# Emulator.net
KiCad netlist of a schematic drawn in Altium Designer
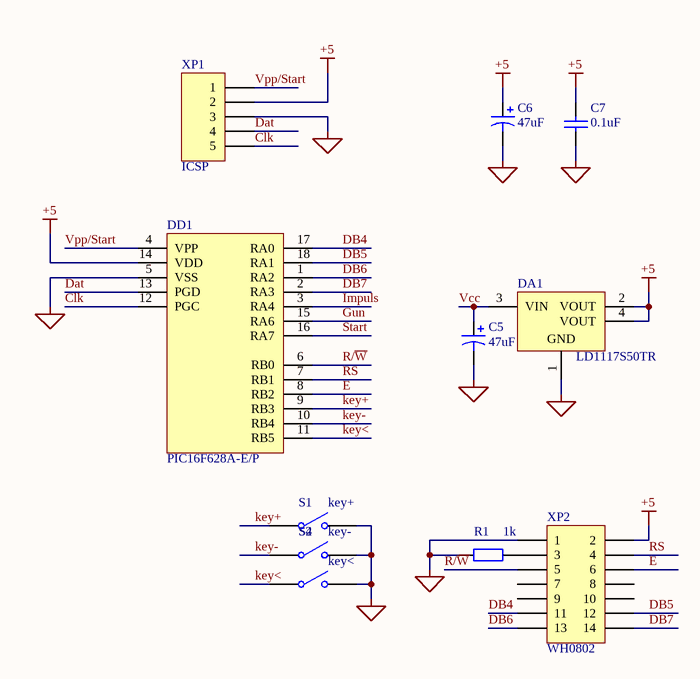
[diagram p0: Emulator.SchDoc]

(export (version "E")
  (design (tool "Eeschema 10.0.6"))
  (components
    (comp (ref "C5")
      (value "47uF")
      (footprint "TC3528-1411")
      (description "Polarized Capacitor (Radial)")
      (fields (field (name "Comment") "Cap Pol1") (field (name "PUBLISHER") "Altium Limited"))
      (libsource (lib "Miscellaneous Devices") (part "Cap Pol1"))
    )
    (comp (ref "C6")
      (value "47uF")
      (footprint "TC3528-1411")
      (description "Polarized Capacitor (Radial)")
      (fields (field (name "Comment") "Cap Pol1") (field (name "PUBLISHER") "Altium Limited"))
      (libsource (lib "Miscellaneous Devices") (part "Cap Pol1"))
    )
    (comp (ref "C7")
      (value "0.1uF")
      (footprint "CAPC2012N")
      (description "Capacitor")
      (fields (field (name "Comment") "Cap") (field (name "PUBLISHER") "Altium Limited"))
      (libsource (lib "Miscellaneous Devices") (part "Cap"))
    )
    (comp (ref "DA1")
      (value "LD1117S50TR")
      (footprint "SOT-223_N")
      (description "Fixed Low Drop Positive Voltage Regulator, 5V, 4-Pin SOT-223, Tape and Reel")
      (libsource (lib "STMicroelectronics Power Management Linear Regulator") (part "LD1117S50TR"))
    )
    (comp (ref "DD1")
      (value "PIC16F628A-E/P")
      (footprint "SOIC127P1030-18N")
      (fields (field (name "PUBLISHER") "Altium Limited"))
      (libsource (lib "Emulator") (part "PIC16F628A-E/P"))
    )
    (comp (ref "R1")
      (value "1k")
      (footprint "RESC2012N")
      (description "Resistor")
      (fields (field (name "Comment") "es2") (field (name "PUBLISHER") "Altium Limited"))
      (libsource (lib "Miscellaneous Devices") (part "Res2"))
    )
    (comp (ref "S1")
      (value "key+")
      (footprint "SPST-2")
      (description "Single-Pole, Single-Throw Switch")
      (fields (field (name "PUBLISHER") "Altium Limited"))
      (libsource (lib "Miscellaneous Devices") (part "SW-SPST"))
    )
    (comp (ref "S2")
      (value "key-")
      (footprint "SPST-2")
      (description "Single-Pole, Single-Throw Switch")
      (fields (field (name "PUBLISHER") "Altium Limited"))
      (libsource (lib "Miscellaneous Devices") (part "SW-SPST"))
    )
    (comp (ref "S4")
      (value "key<")
      (footprint "SPST-2")
      (description "Single-Pole, Single-Throw Switch")
      (fields (field (name "PUBLISHER") "Altium Limited"))
      (libsource (lib "Miscellaneous Devices") (part "SW-SPST"))
    )
    (comp (ref "XP1")
      (value "ICSP")
      (footprint "HDR1X5")
      (description "Header, 5-Pin")
      (fields (field (name "PUBLISHER") "Altium Limited"))
      (libsource (lib "Miscellaneous Connectors") (part "Header 5"))
    )
    (comp (ref "XP2")
      (value "WH0802")
      (footprint "HDR2X7")
      (description "Header, 7-Pin, Dual row")
      (fields (field (name "PUBLISHER") "Altium Limited"))
      (libsource (lib "Miscellaneous Connectors") (part "Header 7X2"))
    )
  )
  (nets
    (net (code "1") (name "+5") (class "Default")
      (node (ref "C6") (pin "1") (pinfunction "1_1") (pintype "passive"))
      (node (ref "C7") (pin "2") (pinfunction "2_2") (pintype "passive"))
      (node (ref "DA1") (pin "2") (pinfunction "VOUT_2") (pintype "power_in"))
      (node (ref "DA1") (pin "4") (pinfunction "VOUT_4") (pintype "power_in"))
      (node (ref "DD1") (pin "14") (pinfunction "VDD_14") (pintype "power_in"))
      (node (ref "XP1") (pin "2") (pinfunction "2_2") (pintype "passive"))
      (node (ref "XP2") (pin "2") (pinfunction "2_2") (pintype "passive"))
    )
    (net (code "2") (name "/Clk") (class "Default")
      (node (ref "DD1") (pin "12") (pinfunction "PGC_12") (pintype "passive"))
      (node (ref "XP1") (pin "5") (pinfunction "5_5") (pintype "passive"))
    )
    (net (code "3") (name "/DB4") (class "Default")
      (node (ref "DD1") (pin "17") (pinfunction "RA0_17") (pintype "passive"))
      (node (ref "XP2") (pin "11") (pinfunction "11_11") (pintype "passive"))
    )
    (net (code "4") (name "/DB5") (class "Default")
      (node (ref "DD1") (pin "18") (pinfunction "RA1_18") (pintype "passive"))
      (node (ref "XP2") (pin "12") (pinfunction "12_12") (pintype "passive"))
    )
    (net (code "5") (name "/DB6") (class "Default")
      (node (ref "DD1") (pin "1") (pinfunction "RA2_1") (pintype "passive"))
      (node (ref "XP2") (pin "13") (pinfunction "13_13") (pintype "passive"))
    )
    (net (code "6") (name "/DB7") (class "Default")
      (node (ref "DD1") (pin "2") (pinfunction "RA3_2") (pintype "passive"))
      (node (ref "XP2") (pin "14") (pinfunction "14_14") (pintype "passive"))
    )
    (net (code "7") (name "/Dat") (class "Default")
      (node (ref "DD1") (pin "13") (pinfunction "PGD_13") (pintype "passive"))
      (node (ref "XP1") (pin "4") (pinfunction "4_4") (pintype "passive"))
    )
    (net (code "8") (name "/E") (class "Default")
      (node (ref "DD1") (pin "8") (pinfunction "RB2_8") (pintype "passive"))
      (node (ref "XP2") (pin "6") (pinfunction "6_6") (pintype "passive"))
    )
    (net (code "9") (name "/Gun") (class "Default")
      (node (ref "DD1") (pin "15") (pinfunction "RA6_15") (pintype "passive"))
    )
    (net (code "10") (name "/Impuls") (class "Default")
      (node (ref "DD1") (pin "3") (pinfunction "RA4_3") (pintype "passive"))
    )
    (net (code "11") (name "/RS") (class "Default")
      (node (ref "DD1") (pin "7") (pinfunction "RB1_7") (pintype "passive"))
      (node (ref "XP2") (pin "4") (pinfunction "4_4") (pintype "passive"))
    )
    (net (code "12") (name "/R{slash}~{W}") (class "Default")
      (node (ref "DD1") (pin "6") (pinfunction "RB0_6") (pintype "passive"))
      (node (ref "XP2") (pin "5") (pinfunction "5_5") (pintype "passive"))
    )
    (net (code "13") (name "/Start") (class "Default")
      (node (ref "DD1") (pin "16") (pinfunction "RA7_16") (pintype "passive"))
    )
    (net (code "14") (name "/Vcc") (class "Default")
      (node (ref "C5") (pin "1") (pinfunction "1_1") (pintype "passive"))
      (node (ref "DA1") (pin "3") (pinfunction "VIN_3") (pintype "power_in"))
    )
    (net (code "15") (name "/Vpp{slash}Start") (class "Default")
      (node (ref "DD1") (pin "4") (pinfunction "VPP_4") (pintype "passive"))
      (node (ref "XP1") (pin "1") (pinfunction "1_1") (pintype "passive"))
    )
    (net (code "16") (name "/key+") (class "Default")
      (node (ref "DD1") (pin "9") (pinfunction "RB3_9") (pintype "passive"))
      (node (ref "S1") (pin "1") (pinfunction "COMMON_1") (pintype "passive"))
    )
    (net (code "17") (name "/key-") (class "Default")
      (node (ref "DD1") (pin "10") (pinfunction "RB4_10") (pintype "passive"))
      (node (ref "S2") (pin "1") (pinfunction "COMMON_1") (pintype "passive"))
    )
    (net (code "18") (name "/key<") (class "Default")
      (node (ref "DD1") (pin "11") (pinfunction "RB5_11") (pintype "passive"))
      (node (ref "S4") (pin "1") (pinfunction "COMMON_1") (pintype "passive"))
    )
    (net (code "19") (name "GND") (class "Default")
      (node (ref "C5") (pin "2") (pinfunction "2_2") (pintype "passive"))
      (node (ref "C6") (pin "2") (pinfunction "2_2") (pintype "passive"))
      (node (ref "C7") (pin "1") (pinfunction "1_1") (pintype "passive"))
      (node (ref "DA1") (pin "1") (pinfunction "GND_1") (pintype "power_in"))
      (node (ref "DD1") (pin "5") (pinfunction "VSS_5") (pintype "power_in"))
      (node (ref "R1") (pin "2") (pinfunction "2_2") (pintype "passive"))
      (node (ref "S1") (pin "2") (pinfunction "NO_2") (pintype "passive"))
      (node (ref "S2") (pin "2") (pinfunction "NO_2") (pintype "passive"))
      (node (ref "S4") (pin "2") (pinfunction "NO_2") (pintype "passive"))
      (node (ref "XP1") (pin "3") (pinfunction "3_3") (pintype "passive"))
      (node (ref "XP2") (pin "1") (pinfunction "1_1") (pintype "passive"))
    )
    (net (code "20") (name "Net-(R1-Pad1)") (class "Default")
      (node (ref "R1") (pin "1") (pinfunction "1_1") (pintype "passive"))
      (node (ref "XP2") (pin "3") (pinfunction "3_3") (pintype "passive"))
    )
    (net (code "21") (name "unconnected-(XP2-Pad7)") (class "Default")
      (node (ref "XP2") (pin "7") (pinfunction "7_7") (pintype "passive"))
    )
    (net (code "22") (name "unconnected-(XP2-Pad8)") (class "Default")
      (node (ref "XP2") (pin "8") (pinfunction "8_8") (pintype "passive"))
    )
    (net (code "23") (name "unconnected-(XP2-Pad9)") (class "Default")
      (node (ref "XP2") (pin "9") (pinfunction "9_9") (pintype "passive"))
    )
    (net (code "24") (name "unconnected-(XP2-Pad10)") (class "Default")
      (node (ref "XP2") (pin "10") (pinfunction "10_10") (pintype "passive"))
    )
  )
)
